# FPGA.net
KiCad netlist of a schematic drawn in Altium Designer
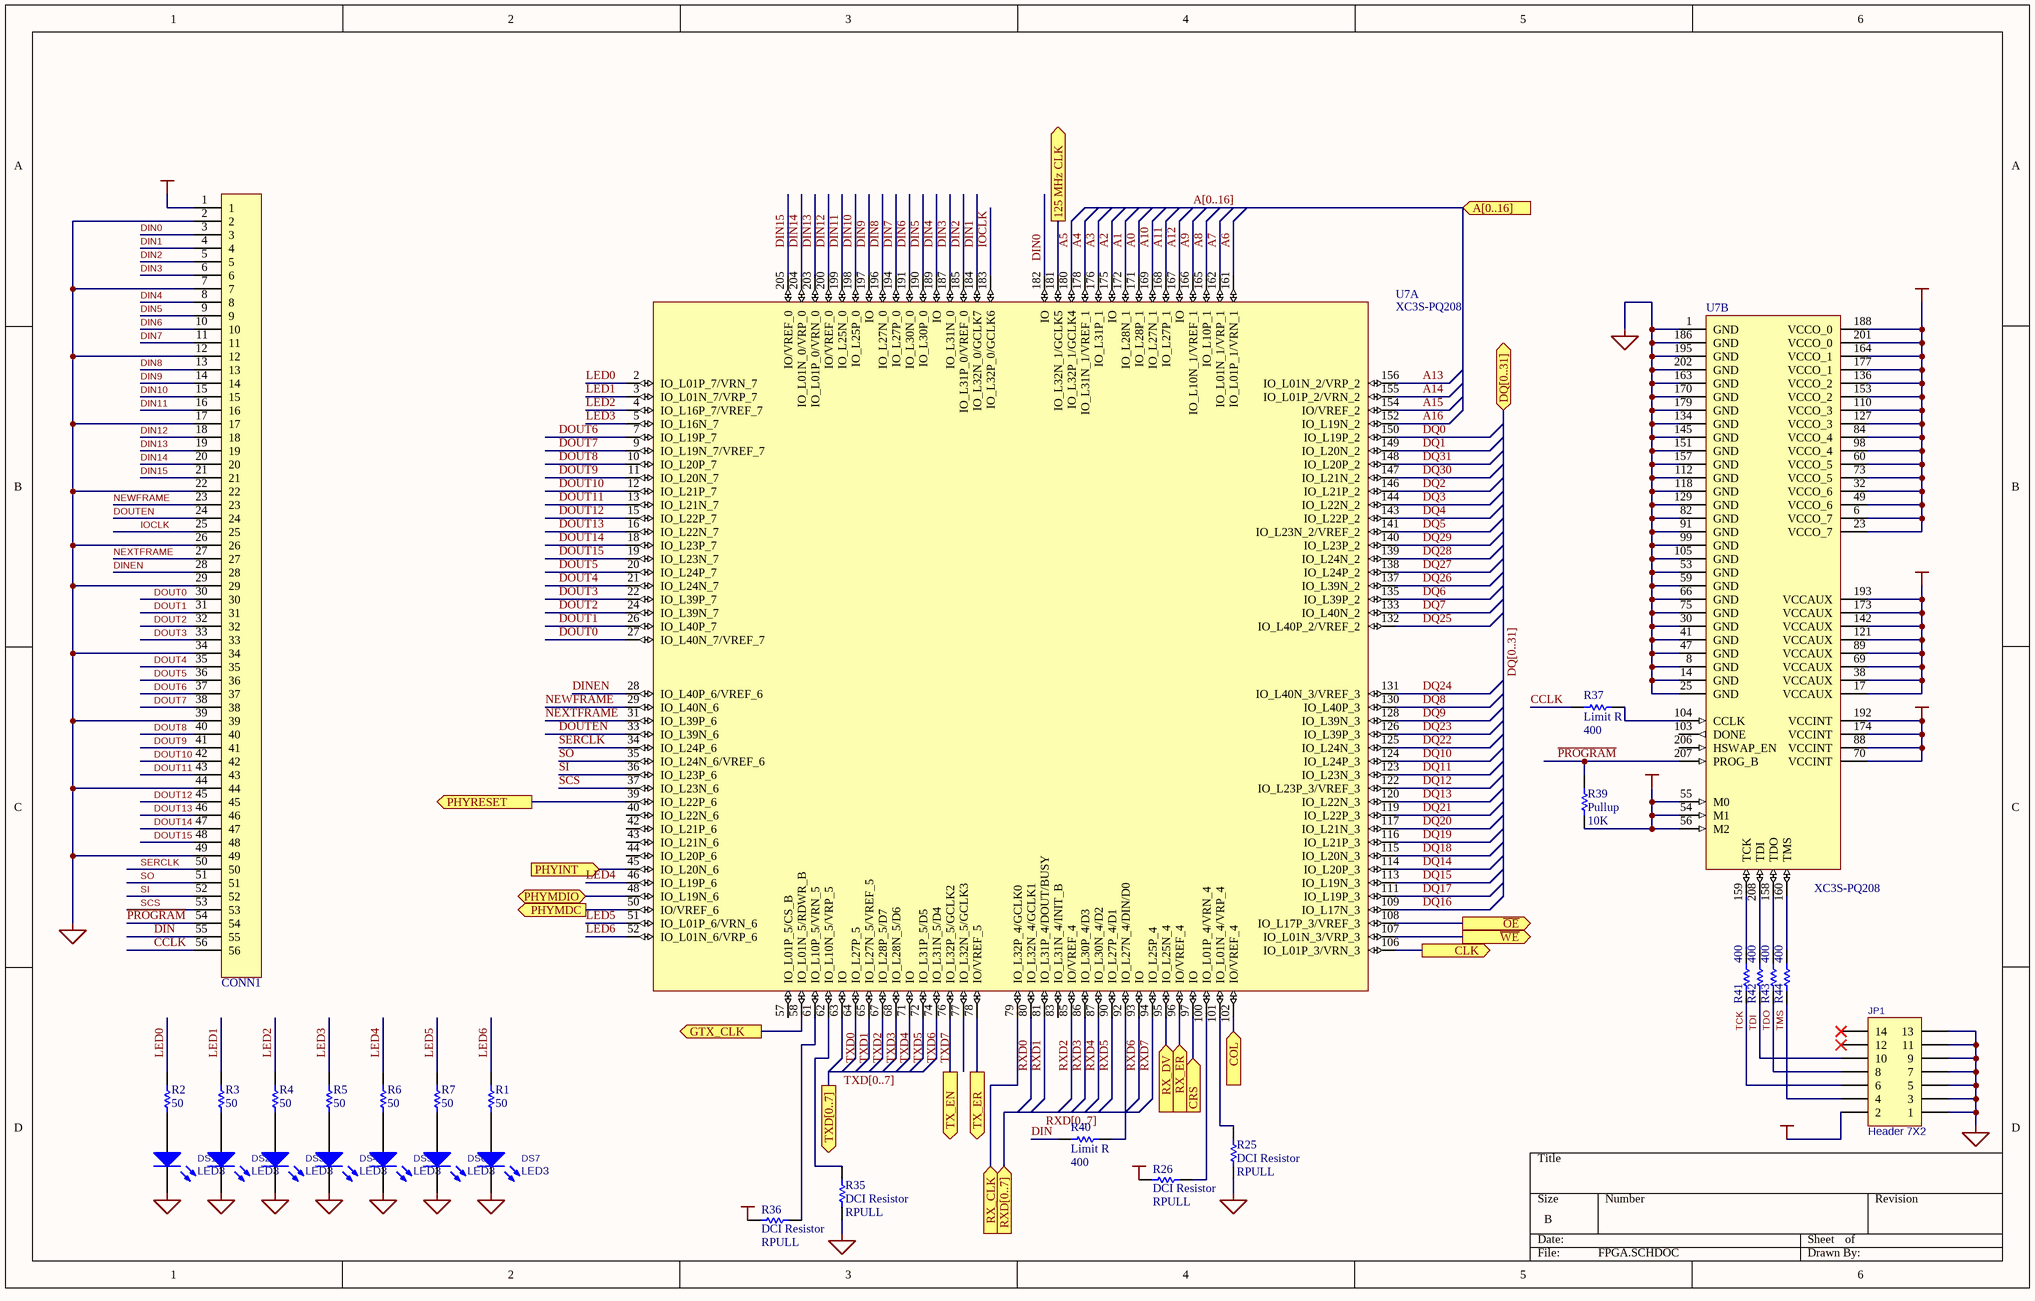
[diagram p0: FPGA.SCHDOC]

(export (version "E")
  (design (tool "Eeschema 10.0.6"))
  (components
    (comp (ref "CONN1") (value "CON56B") (footprint "HDR56F") (libsource (lib "parts") (part "CON56B")))
    (comp (ref "DS1")
      (value "LED3")
      (footprint "SMD _LED")
      (description "Typical BLUE SiC LED")
      (fields (field (name "PUBLISHER") "Altium Limited"))
      (libsource (lib "Miscellaneous Devices") (part "LED3"))
    )
    (comp (ref "DS2")
      (value "LED3")
      (footprint "SMD _LED")
      (description "Typical BLUE SiC LED")
      (fields (field (name "PUBLISHER") "Altium Limited"))
      (libsource (lib "Miscellaneous Devices") (part "LED3"))
    )
    (comp (ref "DS3")
      (value "LED3")
      (footprint "SMD _LED")
      (description "Typical BLUE SiC LED")
      (fields (field (name "PUBLISHER") "Altium Limited"))
      (libsource (lib "Miscellaneous Devices") (part "LED3"))
    )
    (comp (ref "DS4")
      (value "LED3")
      (footprint "SMD _LED")
      (description "Typical BLUE SiC LED")
      (fields (field (name "PUBLISHER") "Altium Limited"))
      (libsource (lib "Miscellaneous Devices") (part "LED3"))
    )
    (comp (ref "DS5")
      (value "LED3")
      (footprint "SMD _LED")
      (description "Typical BLUE SiC LED")
      (fields (field (name "PUBLISHER") "Altium Limited"))
      (libsource (lib "Miscellaneous Devices") (part "LED3"))
    )
    (comp (ref "DS6")
      (value "LED3")
      (footprint "SMD _LED")
      (description "Typical BLUE SiC LED")
      (fields (field (name "PUBLISHER") "Altium Limited"))
      (libsource (lib "Miscellaneous Devices") (part "LED3"))
    )
    (comp (ref "DS7")
      (value "LED3")
      (footprint "SMD _LED")
      (description "Typical BLUE SiC LED")
      (fields (field (name "PUBLISHER") "Altium Limited"))
      (libsource (lib "Miscellaneous Devices") (part "LED3"))
    )
    (comp (ref "JP1")
      (value "Header 7X2")
      (footprint "HDR2x7-2mm")
      (description "Header, 7-Pin, Dual row")
      (fields (field (name "MANUFACTURER") "Generic Components") (field (name "PUBLISHER") "Altium Limited"))
      (libsource (lib "Miscellaneous Connectors") (part "Header 7X2"))
    )
    (comp (ref "R1")
      (value "50")
      (footprint "0603")
      (description "Standard Passive Resistor")
      (fields (field (name "Comment") "RESISTOR"))
      (libsource (lib "parts") (part "RESISTOR"))
    )
    (comp (ref "R2")
      (value "50")
      (footprint "0603")
      (description "Standard Passive Resistor")
      (fields (field (name "Comment") "RESISTOR"))
      (libsource (lib "parts") (part "RESISTOR"))
    )
    (comp (ref "R3")
      (value "50")
      (footprint "0603")
      (description "Standard Passive Resistor")
      (fields (field (name "Comment") "RESISTOR"))
      (libsource (lib "parts") (part "RESISTOR"))
    )
    (comp (ref "R4")
      (value "50")
      (footprint "0603")
      (description "Standard Passive Resistor")
      (fields (field (name "Comment") "RESISTOR"))
      (libsource (lib "parts") (part "RESISTOR"))
    )
    (comp (ref "R5")
      (value "50")
      (footprint "0603")
      (description "Standard Passive Resistor")
      (fields (field (name "Comment") "RESISTOR"))
      (libsource (lib "parts") (part "RESISTOR"))
    )
    (comp (ref "R6")
      (value "50")
      (footprint "0603")
      (description "Standard Passive Resistor")
      (fields (field (name "Comment") "RESISTOR"))
      (libsource (lib "parts") (part "RESISTOR"))
    )
    (comp (ref "R7")
      (value "50")
      (footprint "0603")
      (description "Standard Passive Resistor")
      (fields (field (name "Comment") "RESISTOR"))
      (libsource (lib "parts") (part "RESISTOR"))
    )
    (comp (ref "R25")
      (value "DCI Resistor")
      (footprint "0603")
      (description "Resistor")
      (fields
        (field (name "MANUFACTURER") "Generic Components")
        (field (name "ALTIUM_VALUE") "RPULL")
        (field (name "PUBLISHER") "Altium Limited")
      )
      (libsource (lib "Miscellaneous Devices") (part "Res1"))
    )
    (comp (ref "R26")
      (value "DCI Resistor")
      (footprint "0603")
      (description "Resistor")
      (fields
        (field (name "MANUFACTURER") "Generic Components")
        (field (name "ALTIUM_VALUE") "RPULL")
        (field (name "PUBLISHER") "Altium Limited")
      )
      (libsource (lib "Miscellaneous Devices") (part "Res1"))
    )
    (comp (ref "R35")
      (value "DCI Resistor")
      (footprint "0603")
      (description "Resistor")
      (fields
        (field (name "MANUFACTURER") "Generic Components")
        (field (name "ALTIUM_VALUE") "RPULL")
        (field (name "PUBLISHER") "Altium Limited")
      )
      (libsource (lib "Miscellaneous Devices") (part "Res1"))
    )
    (comp (ref "R36")
      (value "DCI Resistor")
      (footprint "0603")
      (description "Resistor")
      (fields
        (field (name "MANUFACTURER") "Generic Components")
        (field (name "ALTIUM_VALUE") "RPULL")
        (field (name "PUBLISHER") "Altium Limited")
      )
      (libsource (lib "Miscellaneous Devices") (part "Res1"))
    )
    (comp (ref "R37")
      (value "Limit R")
      (footprint "0603")
      (description "Standard Passive Resistor")
      (fields (field (name "ALTIUM_VALUE") "400"))
      (libsource (lib "parts") (part "RESISTOR"))
    )
    (comp (ref "R39")
      (value "Pullup")
      (footprint "0603")
      (description "Resistor")
      (fields
        (field (name "MANUFACTURER") "Generic Components")
        (field (name "ALTIUM_VALUE") "10K")
        (field (name "PUBLISHER") "Altium Limited")
      )
      (libsource (lib "Miscellaneous Devices") (part "Res1"))
    )
    (comp (ref "R40")
      (value "Limit R")
      (footprint "0603")
      (description "Standard Passive Resistor")
      (fields (field (name "ALTIUM_VALUE") "400"))
      (libsource (lib "parts") (part "RESISTOR"))
    )
    (comp (ref "R41")
      (value "400")
      (footprint "0603")
      (description "Standard Passive Resistor")
      (fields (field (name "Comment") "RESISTOR"))
      (libsource (lib "parts") (part "RESISTOR"))
    )
    (comp (ref "R42")
      (value "400")
      (footprint "0603")
      (description "Standard Passive Resistor")
      (fields (field (name "Comment") "RESISTOR"))
      (libsource (lib "parts") (part "RESISTOR"))
    )
    (comp (ref "R43")
      (value "400")
      (footprint "0603")
      (description "Standard Passive Resistor")
      (fields (field (name "Comment") "RESISTOR"))
      (libsource (lib "parts") (part "RESISTOR"))
    )
    (comp (ref "R44")
      (value "400")
      (footprint "0603")
      (description "Standard Passive Resistor")
      (fields (field (name "Comment") "RESISTOR"))
      (libsource (lib "parts") (part "RESISTOR"))
    )
    (comp (ref "U7")
      (value "XC3S-PQ208")
      (footprint "F-QFP28X28-G208/Z32N")
      (description "Xilinx Spartan-3 PQ208")
      (libsource (lib "My devices") (part "XC3S-PQ208"))
    )
  )
  (nets
    (net (code "1") (name "+1.2VCC") (class "Default")
      (node (ref "U7") (pin "174") (pinfunction "VCCINT_174") (pintype "power_in"))
      (node (ref "U7") (pin "192") (pinfunction "VCCINT_192") (pintype "power_in"))
      (node (ref "U7") (pin "70") (pinfunction "VCCINT_70") (pintype "power_in"))
      (node (ref "U7") (pin "88") (pinfunction "VCCINT_88") (pintype "power_in"))
    )
    (net (code "2") (name "+2.5VCC") (class "Default")
      (node (ref "U7") (pin "121") (pinfunction "VCCAUX_121") (pintype "power_in"))
      (node (ref "U7") (pin "142") (pinfunction "VCCAUX_142") (pintype "power_in"))
      (node (ref "U7") (pin "17") (pinfunction "VCCAUX_17") (pintype "power_in"))
      (node (ref "U7") (pin "173") (pinfunction "VCCAUX_173") (pintype "power_in"))
      (node (ref "U7") (pin "193") (pinfunction "VCCAUX_193") (pintype "power_in"))
      (node (ref "U7") (pin "38") (pinfunction "VCCAUX_38") (pintype "power_in"))
      (node (ref "U7") (pin "69") (pinfunction "VCCAUX_69") (pintype "power_in"))
      (node (ref "U7") (pin "89") (pinfunction "VCCAUX_89") (pintype "power_in"))
    )
    (net (code "3") (name "/125 MHz CLK") (class "Default")
      (node (ref "U7") (pin "181") (pinfunction "IO_L32N_1/GCLK5_181") (pintype "bidirectional"))
    )
    (net (code "4") (name "/A0") (class "Default")
      (node (ref "U7") (pin "171") (pinfunction "IO_L28P_1_171") (pintype "bidirectional"))
    )
    (net (code "5") (name "/A1") (class "Default")
      (node (ref "U7") (pin "172") (pinfunction "IO_L28N_1_172") (pintype "bidirectional"))
    )
    (net (code "6") (name "/A2") (class "Default")
      (node (ref "U7") (pin "175") (pinfunction "IO_175") (pintype "bidirectional"))
    )
    (net (code "7") (name "/A3") (class "Default")
      (node (ref "U7") (pin "176") (pinfunction "IO_L31P_1_176") (pintype "bidirectional"))
    )
    (net (code "8") (name "/A4") (class "Default")
      (node (ref "U7") (pin "178") (pinfunction "IO_L31N_1/VREF_1_178") (pintype "bidirectional"))
    )
    (net (code "9") (name "/A5") (class "Default")
      (node (ref "U7") (pin "180") (pinfunction "IO_L32P_1/GCLK4_180") (pintype "bidirectional"))
    )
    (net (code "10") (name "/A6") (class "Default")
      (node (ref "U7") (pin "161") (pinfunction "IO_L01P_1/VRN_1_161") (pintype "bidirectional"))
    )
    (net (code "11") (name "/A7") (class "Default")
      (node (ref "U7") (pin "162") (pinfunction "IO_L01N_1/VRP_1_162") (pintype "bidirectional"))
    )
    (net (code "12") (name "/A8") (class "Default")
      (node (ref "U7") (pin "165") (pinfunction "IO_L10P_1_165") (pintype "bidirectional"))
    )
    (net (code "13") (name "/A9") (class "Default")
      (node (ref "U7") (pin "166") (pinfunction "IO_L10N_1/VREF_1_166") (pintype "bidirectional"))
    )
    (net (code "14") (name "/A10") (class "Default")
      (node (ref "U7") (pin "169") (pinfunction "IO_L27N_1_169") (pintype "bidirectional"))
    )
    (net (code "15") (name "/A11") (class "Default")
      (node (ref "U7") (pin "168") (pinfunction "IO_L27P_1_168") (pintype "bidirectional"))
    )
    (net (code "16") (name "/A12") (class "Default")
      (node (ref "U7") (pin "167") (pinfunction "IO_167") (pintype "bidirectional"))
    )
    (net (code "17") (name "/A13") (class "Default")
      (node (ref "U7") (pin "156") (pinfunction "IO_L01N_2/VRP_2_156") (pintype "bidirectional"))
    )
    (net (code "18") (name "/A14") (class "Default")
      (node (ref "U7") (pin "155") (pinfunction "IO_L01P_2/VRN_2_155") (pintype "bidirectional"))
    )
    (net (code "19") (name "/A15") (class "Default")
      (node (ref "U7") (pin "154") (pinfunction "IO/VREF_2_154") (pintype "bidirectional"))
    )
    (net (code "20") (name "/A16") (class "Default")
      (node (ref "U7") (pin "152") (pinfunction "IO_L19N_2_152") (pintype "bidirectional"))
    )
    (net (code "22") (name "/CCLK") (class "Default")
      (node (ref "CONN1") (pin "56") (pinfunction "56_56") (pintype "passive"))
      (node (ref "R37") (pin "2") (pintype "passive"))
    )
    (net (code "23") (name "/CLK") (class "Default")
      (node (ref "U7") (pin "106") (pinfunction "IO_L01P_3/VRN_3_106") (pintype "bidirectional"))
    )
    (net (code "24") (name "/COL") (class "Default")
      (node (ref "U7") (pin "102") (pinfunction "IO/VREF_4_102") (pintype "bidirectional"))
    )
    (net (code "25") (name "/CRS") (class "Default")
      (node (ref "U7") (pin "97") (pinfunction "IO_97") (pintype "bidirectional"))
    )
    (net (code "26") (name "/DIN") (class "Default")
      (node (ref "CONN1") (pin "55") (pinfunction "55_55") (pintype "passive"))
      (node (ref "R40") (pin "2") (pintype "passive"))
    )
    (net (code "27") (name "/DIN0") (class "Default")
      (node (ref "CONN1") (pin "3") (pinfunction "3_3") (pintype "passive"))
      (node (ref "U7") (pin "182") (pinfunction "IO_182") (pintype "bidirectional"))
    )
    (net (code "28") (name "/DIN1") (class "Default")
      (node (ref "CONN1") (pin "4") (pinfunction "4_4") (pintype "passive"))
      (node (ref "U7") (pin "184") (pinfunction "IO_L32N_0/GCLK7_184") (pintype "bidirectional"))
    )
    (net (code "29") (name "/DIN2") (class "Default")
      (node (ref "CONN1") (pin "5") (pinfunction "5_5") (pintype "passive"))
      (node (ref "U7") (pin "185") (pinfunction "IO_L31P_0/VREF_0_185") (pintype "bidirectional"))
    )
    (net (code "30") (name "/DIN3") (class "Default")
      (node (ref "CONN1") (pin "6") (pinfunction "6_6") (pintype "passive"))
      (node (ref "U7") (pin "187") (pinfunction "IO_L31N_0_187") (pintype "bidirectional"))
    )
    (net (code "31") (name "/DIN4") (class "Default")
      (node (ref "CONN1") (pin "8") (pinfunction "8_8") (pintype "passive"))
      (node (ref "U7") (pin "189") (pinfunction "IO_189") (pintype "bidirectional"))
    )
    (net (code "32") (name "/DIN5") (class "Default")
      (node (ref "CONN1") (pin "9") (pinfunction "9_9") (pintype "passive"))
      (node (ref "U7") (pin "190") (pinfunction "IO_L30P_0_190") (pintype "bidirectional"))
    )
    (net (code "33") (name "/DIN6") (class "Default")
      (node (ref "CONN1") (pin "10") (pinfunction "10_10") (pintype "passive"))
      (node (ref "U7") (pin "191") (pinfunction "IO_L30N_0_191") (pintype "bidirectional"))
    )
    (net (code "34") (name "/DIN7") (class "Default")
      (node (ref "CONN1") (pin "11") (pinfunction "11_11") (pintype "passive"))
      (node (ref "U7") (pin "194") (pinfunction "IO_L27P_0_194") (pintype "bidirectional"))
    )
    (net (code "35") (name "/DIN8") (class "Default")
      (node (ref "CONN1") (pin "13") (pinfunction "13_13") (pintype "passive"))
      (node (ref "U7") (pin "196") (pinfunction "IO_L27N_0_196") (pintype "bidirectional"))
    )
    (net (code "36") (name "/DIN9") (class "Default")
      (node (ref "CONN1") (pin "14") (pinfunction "14_14") (pintype "passive"))
      (node (ref "U7") (pin "197") (pinfunction "IO_197") (pintype "bidirectional"))
    )
    (net (code "37") (name "/DIN10") (class "Default")
      (node (ref "CONN1") (pin "15") (pinfunction "15_15") (pintype "passive"))
      (node (ref "U7") (pin "198") (pinfunction "IO_L25P_0_198") (pintype "bidirectional"))
    )
    (net (code "38") (name "/DIN11") (class "Default")
      (node (ref "CONN1") (pin "16") (pinfunction "16_16") (pintype "passive"))
      (node (ref "U7") (pin "199") (pinfunction "IO_L25N_0_199") (pintype "bidirectional"))
    )
    (net (code "39") (name "/DIN12") (class "Default")
      (node (ref "CONN1") (pin "18") (pinfunction "18_18") (pintype "passive"))
      (node (ref "U7") (pin "200") (pinfunction "IO/VREF_0_200") (pintype "bidirectional"))
    )
    (net (code "40") (name "/DIN13") (class "Default")
      (node (ref "CONN1") (pin "19") (pinfunction "19_19") (pintype "passive"))
      (node (ref "U7") (pin "203") (pinfunction "IO_L01P_0/VRN_0_203") (pintype "bidirectional"))
    )
    (net (code "41") (name "/DIN14") (class "Default")
      (node (ref "CONN1") (pin "20") (pinfunction "20_20") (pintype "passive"))
      (node (ref "U7") (pin "204") (pinfunction "IO_L01N_0/VRP_0_204") (pintype "bidirectional"))
    )
    (net (code "42") (name "/DIN15") (class "Default")
      (node (ref "CONN1") (pin "21") (pinfunction "21_21") (pintype "passive"))
      (node (ref "U7") (pin "205") (pinfunction "IO/VREF_0_205") (pintype "bidirectional"))
    )
    (net (code "43") (name "/DINEN") (class "Default")
      (node (ref "CONN1") (pin "28") (pinfunction "28_28") (pintype "passive"))
      (node (ref "U7") (pin "28") (pinfunction "IO_L40P_6/VREF_6_28") (pintype "bidirectional"))
    )
    (net (code "44") (name "/DOUT0") (class "Default")
      (node (ref "CONN1") (pin "30") (pinfunction "30_30") (pintype "passive"))
      (node (ref "U7") (pin "27") (pinfunction "IO_L40N_7/VREF_7_27") (pintype "bidirectional"))
    )
    (net (code "45") (name "/DOUT1") (class "Default")
      (node (ref "CONN1") (pin "31") (pinfunction "31_31") (pintype "passive"))
      (node (ref "U7") (pin "26") (pinfunction "IO_L40P_7_26") (pintype "bidirectional"))
    )
    (net (code "46") (name "/DOUT2") (class "Default")
      (node (ref "CONN1") (pin "32") (pinfunction "32_32") (pintype "passive"))
      (node (ref "U7") (pin "24") (pinfunction "IO_L39N_7_24") (pintype "bidirectional"))
    )
    (net (code "47") (name "/DOUT3") (class "Default")
      (node (ref "CONN1") (pin "33") (pinfunction "33_33") (pintype "passive"))
      (node (ref "U7") (pin "22") (pinfunction "IO_L39P_7_22") (pintype "bidirectional"))
    )
    (net (code "48") (name "/DOUT4") (class "Default")
      (node (ref "CONN1") (pin "35") (pinfunction "35_35") (pintype "passive"))
      (node (ref "U7") (pin "21") (pinfunction "IO_L24N_7_21") (pintype "bidirectional"))
    )
    (net (code "49") (name "/DOUT5") (class "Default")
      (node (ref "CONN1") (pin "36") (pinfunction "36_36") (pintype "passive"))
      (node (ref "U7") (pin "20") (pinfunction "IO_L24P_7_20") (pintype "bidirectional"))
    )
    (net (code "50") (name "/DOUT6") (class "Default")
      (node (ref "CONN1") (pin "37") (pinfunction "37_37") (pintype "passive"))
      (node (ref "U7") (pin "7") (pinfunction "IO_L19P_7_7") (pintype "bidirectional"))
    )
    (net (code "51") (name "/DOUT7") (class "Default")
      (node (ref "CONN1") (pin "38") (pinfunction "38_38") (pintype "passive"))
      (node (ref "U7") (pin "9") (pinfunction "IO_L19N_7/VREF_7_9") (pintype "bidirectional"))
    )
    (net (code "52") (name "/DOUT8") (class "Default")
      (node (ref "CONN1") (pin "40") (pinfunction "40_40") (pintype "passive"))
      (node (ref "U7") (pin "10") (pinfunction "IO_L20P_7_10") (pintype "bidirectional"))
    )
    (net (code "53") (name "/DOUT9") (class "Default")
      (node (ref "CONN1") (pin "41") (pinfunction "41_41") (pintype "passive"))
      (node (ref "U7") (pin "11") (pinfunction "IO_L20N_7_11") (pintype "bidirectional"))
    )
    (net (code "54") (name "/DOUT10") (class "Default")
      (node (ref "CONN1") (pin "42") (pinfunction "42_42") (pintype "passive"))
      (node (ref "U7") (pin "12") (pinfunction "IO_L21P_7_12") (pintype "bidirectional"))
    )
    (net (code "55") (name "/DOUT11") (class "Default")
      (node (ref "CONN1") (pin "43") (pinfunction "43_43") (pintype "passive"))
      (node (ref "U7") (pin "13") (pinfunction "IO_L21N_7_13") (pintype "bidirectional"))
    )
    (net (code "56") (name "/DOUT12") (class "Default")
      (node (ref "CONN1") (pin "45") (pinfunction "45_45") (pintype "passive"))
      (node (ref "U7") (pin "15") (pinfunction "IO_L22P_7_15") (pintype "bidirectional"))
    )
    (net (code "57") (name "/DOUT13") (class "Default")
      (node (ref "CONN1") (pin "46") (pinfunction "46_46") (pintype "passive"))
      (node (ref "U7") (pin "16") (pinfunction "IO_L22N_7_16") (pintype "bidirectional"))
    )
    (net (code "58") (name "/DOUT14") (class "Default")
      (node (ref "CONN1") (pin "47") (pinfunction "47_47") (pintype "passive"))
      (node (ref "U7") (pin "18") (pinfunction "IO_L23P_7_18") (pintype "bidirectional"))
    )
    (net (code "59") (name "/DOUT15") (class "Default")
      (node (ref "CONN1") (pin "48") (pinfunction "48_48") (pintype "passive"))
      (node (ref "U7") (pin "19") (pinfunction "IO_L23N_7_19") (pintype "bidirectional"))
    )
    (net (code "60") (name "/DOUTEN") (class "Default")
      (node (ref "CONN1") (pin "24") (pinfunction "24_24") (pintype "passive"))
      (node (ref "U7") (pin "33") (pinfunction "IO_L39N_6_33") (pintype "bidirectional"))
    )
    (net (code "61") (name "/DQ0") (class "Default")
      (node (ref "U7") (pin "150") (pinfunction "IO_L19P_2_150") (pintype "bidirectional"))
    )
    (net (code "62") (name "/DQ1") (class "Default")
      (node (ref "U7") (pin "149") (pinfunction "IO_L20N_2_149") (pintype "bidirectional"))
    )
    (net (code "63") (name "/DQ2") (class "Default")
      (node (ref "U7") (pin "146") (pinfunction "IO_L21P_2_146") (pintype "bidirectional"))
    )
    (net (code "64") (name "/DQ3") (class "Default")
      (node (ref "U7") (pin "144") (pinfunction "IO_L22N_2_144") (pintype "bidirectional"))
    )
    (net (code "65") (name "/DQ4") (class "Default")
      (node (ref "U7") (pin "143") (pinfunction "IO_L22P_2_143") (pintype "bidirectional"))
    )
    (net (code "66") (name "/DQ5") (class "Default")
      (node (ref "U7") (pin "141") (pinfunction "IO_L23N_2/VREF_2_141") (pintype "bidirectional"))
    )
    (net (code "67") (name "/DQ6") (class "Default")
      (node (ref "U7") (pin "135") (pinfunction "IO_L39P_2_135") (pintype "bidirectional"))
    )
    (net (code "68") (name "/DQ7") (class "Default")
      (node (ref "U7") (pin "133") (pinfunction "IO_L40N_2_133") (pintype "bidirectional"))
    )
    (net (code "69") (name "/DQ8") (class "Default")
      (node (ref "U7") (pin "130") (pinfunction "IO_L40P_3_130") (pintype "bidirectional"))
    )
    (net (code "70") (name "/DQ9") (class "Default")
      (node (ref "U7") (pin "128") (pinfunction "IO_L39N_3_128") (pintype "bidirectional"))
    )
    (net (code "71") (name "/DQ10") (class "Default")
      (node (ref "U7") (pin "124") (pinfunction "IO_L24P_3_124") (pintype "bidirectional"))
    )
    (net (code "72") (name "/DQ11") (class "Default")
      (node (ref "U7") (pin "123") (pinfunction "IO_L23N_3_123") (pintype "bidirectional"))
    )
    (net (code "73") (name "/DQ12") (class "Default")
      (node (ref "U7") (pin "122") (pinfunction "IO_L23P_3/VREF_3_122") (pintype "bidirectional"))
    )
    (net (code "74") (name "/DQ13") (class "Default")
      (node (ref "U7") (pin "120") (pinfunction "IO_L22N_3_120") (pintype "bidirectional"))
    )
    (net (code "75") (name "/DQ14") (class "Default")
      (node (ref "U7") (pin "114") (pinfunction "IO_L20P_3_114") (pintype "bidirectional"))
    )
    (net (code "76") (name "/DQ15") (class "Default")
      (node (ref "U7") (pin "113") (pinfunction "IO_L19N_3_113") (pintype "bidirectional"))
    )
    (net (code "77") (name "/DQ16") (class "Default")
      (node (ref "U7") (pin "109") (pinfunction "IO_L17N_3_109") (pintype "bidirectional"))
    )
    (net (code "78") (name "/DQ17") (class "Default")
      (node (ref "U7") (pin "111") (pinfunction "IO_L19P_3_111") (pintype "bidirectional"))
    )
    (net (code "79") (name "/DQ18") (class "Default")
      (node (ref "U7") (pin "115") (pinfunction "IO_L20N_3_115") (pintype "bidirectional"))
    )
    (net (code "80") (name "/DQ19") (class "Default")
      (node (ref "U7") (pin "116") (pinfunction "IO_L21P_3_116") (pintype "bidirectional"))
    )
    (net (code "81") (name "/DQ20") (class "Default")
      (node (ref "U7") (pin "117") (pinfunction "IO_L21N_3_117") (pintype "bidirectional"))
    )
    (net (code "82") (name "/DQ21") (class "Default")
      (node (ref "U7") (pin "119") (pinfunction "IO_L22P_3_119") (pintype "bidirectional"))
    )
    (net (code "83") (name "/DQ22") (class "Default")
      (node (ref "U7") (pin "125") (pinfunction "IO_L24N_3_125") (pintype "bidirectional"))
    )
    (net (code "84") (name "/DQ23") (class "Default")
      (node (ref "U7") (pin "126") (pinfunction "IO_L39P_3_126") (pintype "bidirectional"))
    )
    (net (code "85") (name "/DQ24") (class "Default")
      (node (ref "U7") (pin "131") (pinfunction "IO_L40N_3/VREF_3_131") (pintype "bidirectional"))
    )
    (net (code "86") (name "/DQ25") (class "Default")
      (node (ref "U7") (pin "132") (pinfunction "IO_L40P_2/VREF_2_132") (pintype "bidirectional"))
    )
    (net (code "87") (name "/DQ26") (class "Default")
      (node (ref "U7") (pin "137") (pinfunction "IO_L39N_2_137") (pintype "bidirectional"))
    )
    (net (code "88") (name "/DQ27") (class "Default")
      (node (ref "U7") (pin "138") (pinfunction "IO_L24P_2_138") (pintype "bidirectional"))
    )
    (net (code "89") (name "/DQ28") (class "Default")
      (node (ref "U7") (pin "139") (pinfunction "IO_L24N_2_139") (pintype "bidirectional"))
    )
    (net (code "90") (name "/DQ29") (class "Default")
      (node (ref "U7") (pin "140") (pinfunction "IO_L23P_2_140") (pintype "bidirectional"))
    )
    (net (code "91") (name "/DQ30") (class "Default")
      (node (ref "U7") (pin "147") (pinfunction "IO_L21N_2_147") (pintype "bidirectional"))
    )
    (net (code "92") (name "/DQ31") (class "Default")
      (node (ref "U7") (pin "148") (pinfunction "IO_L20P_2_148") (pintype "bidirectional"))
    )
    (net (code "94") (name "/GTX_CLK") (class "Default")
      (node (ref "U7") (pin "58") (pinfunction "IO_L01N_5/RDWR_B_58") (pintype "bidirectional"))
    )
    (net (code "95") (name "/IOCLK") (class "Default")
      (node (ref "CONN1") (pin "25") (pinfunction "25_25") (pintype "passive"))
      (node (ref "U7") (pin "183") (pinfunction "IO_L32P_0/GCLK6_183") (pintype "bidirectional"))
    )
    (net (code "96") (name "/LED0") (class "Default")
      (node (ref "R2") (pin "2") (pintype "passive"))
      (node (ref "U7") (pin "2") (pinfunction "IO_L01P_7/VRN_7_2") (pintype "bidirectional"))
    )
    (net (code "97") (name "/LED1") (class "Default")
      (node (ref "R3") (pin "2") (pintype "passive"))
      (node (ref "U7") (pin "3") (pinfunction "IO_L01N_7/VRP_7_3") (pintype "bidirectional"))
    )
    (net (code "98") (name "/LED2") (class "Default")
      (node (ref "R4") (pin "2") (pintype "passive"))
      (node (ref "U7") (pin "4") (pinfunction "IO_L16P_7/VREF_7_4") (pintype "bidirectional"))
    )
    (net (code "99") (name "/LED3") (class "Default")
      (node (ref "R5") (pin "2") (pintype "passive"))
      (node (ref "U7") (pin "5") (pinfunction "IO_L16N_7_5") (pintype "bidirectional"))
    )
    (net (code "100") (name "/LED4") (class "Default")
      (node (ref "R6") (pin "2") (pintype "passive"))
      (node (ref "U7") (pin "46") (pinfunction "IO_L19P_6_46") (pintype "bidirectional"))
    )
    (net (code "101") (name "/LED5") (class "Default")
      (node (ref "R7") (pin "2") (pintype "passive"))
      (node (ref "U7") (pin "51") (pinfunction "IO_L01P_6/VRN_6_51") (pintype "bidirectional"))
    )
    (net (code "102") (name "/LED6") (class "Default")
      (node (ref "R1") (pin "2") (pintype "passive"))
      (node (ref "U7") (pin "52") (pinfunction "IO_L01N_6/VRP_6_52") (pintype "bidirectional"))
    )
    (net (code "103") (name "/NEWFRAME") (class "Default")
      (node (ref "CONN1") (pin "23") (pinfunction "23_23") (pintype "passive"))
      (node (ref "U7") (pin "29") (pinfunction "IO_L40N_6_29") (pintype "bidirectional"))
    )
    (net (code "104") (name "/NEXTFRAME") (class "Default")
      (node (ref "CONN1") (pin "27") (pinfunction "27_27") (pintype "passive"))
      (node (ref "U7") (pin "31") (pinfunction "IO_L39P_6_31") (pintype "bidirectional"))
    )
    (net (code "105") (name "/PHYINT") (class "Default")
      (node (ref "U7") (pin "45") (pinfunction "IO_L20N_6_45") (pintype "bidirectional"))
    )
    (net (code "106") (name "/PHYMDC") (class "Default")
      (node (ref "U7") (pin "50") (pinfunction "IO/VREF_6_50") (pintype "bidirectional"))
    )
    (net (code "107") (name "/PHYMDIO") (class "Default")
      (node (ref "U7") (pin "48") (pinfunction "IO_L19N_6_48") (pintype "bidirectional"))
    )
    (net (code "108") (name "/PHYRESET") (class "Default")
      (node (ref "U7") (pin "39") (pinfunction "IO_L22P_6_39") (pintype "bidirectional"))
    )
    (net (code "109") (name "/RXD0") (class "Default")
      (node (ref "U7") (pin "80") (pinfunction "IO_L32N_4/GCLK1_80") (pintype "bidirectional"))
    )
    (net (code "110") (name "/RXD1") (class "Default")
      (node (ref "U7") (pin "81") (pinfunction "IO_L31P_4/DOUT/BUSY_81") (pintype "bidirectional"))
    )
    (net (code "111") (name "/RXD2") (class "Default")
      (node (ref "U7") (pin "85") (pinfunction "IO/VREF_4_85") (pintype "bidirectional"))
    )
    (net (code "112") (name "/RXD3") (class "Default")
      (node (ref "U7") (pin "86") (pinfunction "IO_L30P_4/D3_86") (pintype "bidirectional"))
    )
    (net (code "113") (name "/RXD4") (class "Default")
      (node (ref "U7") (pin "87") (pinfunction "IO_L30N_4/D2_87") (pintype "bidirectional"))
    )
    (net (code "114") (name "/RXD5") (class "Default")
      (node (ref "U7") (pin "90") (pinfunction "IO_L27P_4/D1_90") (pintype "bidirectional"))
    )
    (net (code "115") (name "/RXD6") (class "Default")
      (node (ref "U7") (pin "93") (pinfunction "IO_93") (pintype "bidirectional"))
    )
    (net (code "116") (name "/RXD7") (class "Default")
      (node (ref "U7") (pin "94") (pinfunction "IO_L25P_4_94") (pintype "bidirectional"))
    )
    (net (code "118") (name "/RX_CLK") (class "Default")
      (node (ref "U7") (pin "79") (pinfunction "IO_L32P_4/GCLK0_79") (pintype "bidirectional"))
    )
    (net (code "119") (name "/RX_DV") (class "Default")
      (node (ref "U7") (pin "95") (pinfunction "IO_L25N_4_95") (pintype "bidirectional"))
    )
    (net (code "120") (name "/RX_ER") (class "Default")
      (node (ref "U7") (pin "96") (pinfunction "IO/VREF_4_96") (pintype "bidirectional"))
    )
    (net (code "121") (name "/SCS") (class "Default")
      (node (ref "CONN1") (pin "53") (pinfunction "53_53") (pintype "passive"))
      (node (ref "U7") (pin "37") (pinfunction "IO_L23N_6_37") (pintype "bidirectional"))
    )
    (net (code "122") (name "/SERCLK") (class "Default")
      (node (ref "CONN1") (pin "50") (pinfunction "50_50") (pintype "passive"))
      (node (ref "U7") (pin "34") (pinfunction "IO_L24P_6_34") (pintype "bidirectional"))
    )
    (net (code "123") (name "/SI") (class "Default")
      (node (ref "CONN1") (pin "52") (pinfunction "52_52") (pintype "passive"))
      (node (ref "U7") (pin "36") (pinfunction "IO_L23P_6_36") (pintype "bidirectional"))
    )
    (net (code "124") (name "/SO") (class "Default")
      (node (ref "CONN1") (pin "51") (pinfunction "51_51") (pintype "passive"))
      (node (ref "U7") (pin "35") (pinfunction "IO_L24N_6/VREF_6_35") (pintype "bidirectional"))
    )
    (net (code "125") (name "/TCK") (class "Default")
      (node (ref "JP1") (pin "6") (pinfunction "6_6") (pintype "passive"))
      (node (ref "R41") (pin "2") (pintype "passive"))
    )
    (net (code "126") (name "/TDI") (class "Default")
      (node (ref "JP1") (pin "10") (pinfunction "10_10") (pintype "passive"))
      (node (ref "R42") (pin "2") (pintype "passive"))
    )
    (net (code "127") (name "/TDO") (class "Default")
      (node (ref "JP1") (pin "8") (pinfunction "8_8") (pintype "passive"))
      (node (ref "R43") (pin "2") (pintype "passive"))
    )
    (net (code "128") (name "/TMS") (class "Default")
      (node (ref "JP1") (pin "4") (pinfunction "4_4") (pintype "passive"))
      (node (ref "R44") (pin "2") (pintype "passive"))
    )
    (net (code "129") (name "/TXD0") (class "Default")
      (node (ref "U7") (pin "63") (pinfunction "IO_63") (pintype "bidirectional"))
    )
    (net (code "130") (name "/TXD1") (class "Default")
      (node (ref "U7") (pin "64") (pinfunction "IO_L27P_5_64") (pintype "bidirectional"))
    )
    (net (code "131") (name "/TXD2") (class "Default")
      (node (ref "U7") (pin "65") (pinfunction "IO_L27N_5/VREF_5_65") (pintype "bidirectional"))
    )
    (net (code "132") (name "/TXD3") (class "Default")
      (node (ref "U7") (pin "67") (pinfunction "IO_L28P_5/D7_67") (pintype "bidirectional"))
    )
    (net (code "133") (name "/TXD4") (class "Default")
      (node (ref "U7") (pin "68") (pinfunction "IO_L28N_5/D6_68") (pintype "bidirectional"))
    )
    (net (code "134") (name "/TXD5") (class "Default")
      (node (ref "U7") (pin "71") (pinfunction "IO_71") (pintype "bidirectional"))
    )
    (net (code "135") (name "/TXD6") (class "Default")
      (node (ref "U7") (pin "72") (pinfunction "IO_L31P_5/D5_72") (pintype "bidirectional"))
    )
    (net (code "136") (name "/TXD7") (class "Default")
      (node (ref "U7") (pin "74") (pinfunction "IO_L31N_5/D4_74") (pintype "bidirectional"))
    )
    (net (code "138") (name "/TX_EN") (class "Default")
      (node (ref "U7") (pin "76") (pinfunction "IO_L32P_5/GCLK2_76") (pintype "bidirectional"))
    )
    (net (code "139") (name "/TX_ER") (class "Default")
      (node (ref "U7") (pin "78") (pinfunction "IO/VREF_5_78") (pintype "bidirectional"))
    )
    (net (code "140") (name "/~{OE}") (class "Default")
      (node (ref "U7") (pin "108") (pinfunction "IO_L17P_3/VREF_3_108") (pintype "bidirectional"))
    )
    (net (code "141") (name "/~{PROGRAM}") (class "Default")
      (node (ref "CONN1") (pin "54") (pinfunction "54_54") (pintype "passive"))
      (node (ref "R39") (pin "1") (pinfunction "1_1") (pintype "passive"))
      (node (ref "U7") (pin "207") (pinfunction "PROG_B_207") (pintype "input"))
    )
    (net (code "142") (name "/~{WE}") (class "Default")
      (node (ref "U7") (pin "107") (pinfunction "IO_L01N_3/VRP_3_107") (pintype "bidirectional"))
    )
    (net (code "143") (name "GND") (class "Default")
      (node (ref "CONN1") (pin "12") (pinfunction "12_12") (pintype "passive"))
      (node (ref "CONN1") (pin "17") (pinfunction "17_17") (pintype "passive"))
      (node (ref "CONN1") (pin "2") (pinfunction "2_2") (pintype "passive"))
      (node (ref "CONN1") (pin "22") (pinfunction "22_22") (pintype "passive"))
      (node (ref "CONN1") (pin "26") (pinfunction "26_26") (pintype "passive"))
      (node (ref "CONN1") (pin "29") (pinfunction "29_29") (pintype "passive"))
      (node (ref "CONN1") (pin "34") (pinfunction "34_34") (pintype "passive"))
      (node (ref "CONN1") (pin "39") (pinfunction "39_39") (pintype "passive"))
      (node (ref "CONN1") (pin "44") (pinfunction "44_44") (pintype "passive"))
      (node (ref "CONN1") (pin "49") (pinfunction "49_49") (pintype "passive"))
      (node (ref "CONN1") (pin "7") (pinfunction "7_7") (pintype "passive"))
      (node (ref "DS1") (pin "2") (pinfunction "K_2") (pintype "passive"))
      (node (ref "DS2") (pin "2") (pinfunction "K_2") (pintype "passive"))
      (node (ref "DS3") (pin "2") (pinfunction "K_2") (pintype "passive"))
      (node (ref "DS4") (pin "2") (pinfunction "K_2") (pintype "passive"))
      (node (ref "DS5") (pin "2") (pinfunction "K_2") (pintype "passive"))
      (node (ref "DS6") (pin "2") (pinfunction "K_2") (pintype "passive"))
      (node (ref "DS7") (pin "2") (pinfunction "K_2") (pintype "passive"))
      (node (ref "JP1") (pin "1") (pinfunction "1_1") (pintype "passive"))
      (node (ref "JP1") (pin "11") (pinfunction "11_11") (pintype "passive"))
      (node (ref "JP1") (pin "13") (pinfunction "13_13") (pintype "passive"))
      (node (ref "JP1") (pin "3") (pinfunction "3_3") (pintype "passive"))
      (node (ref "JP1") (pin "5") (pinfunction "5_5") (pintype "passive"))
      (node (ref "JP1") (pin "7") (pinfunction "7_7") (pintype "passive"))
      (node (ref "JP1") (pin "9") (pinfunction "9_9") (pintype "passive"))
      (node (ref "R25") (pin "1") (pinfunction "1_1") (pintype "passive"))
      (node (ref "R35") (pin "1") (pinfunction "1_1") (pintype "passive"))
      (node (ref "U7") (pin "1") (pinfunction "GND_1") (pintype "power_in"))
      (node (ref "U7") (pin "105") (pinfunction "GND_105") (pintype "power_in"))
      (node (ref "U7") (pin "112") (pinfunction "GND_112") (pintype "power_in"))
      (node (ref "U7") (pin "118") (pinfunction "GND_118") (pintype "power_in"))
      (node (ref "U7") (pin "129") (pinfunction "GND_129") (pintype "power_in"))
      (node (ref "U7") (pin "134") (pinfunction "GND_134") (pintype "power_in"))
      (node (ref "U7") (pin "14") (pinfunction "GND_14") (pintype "power_in"))
      (node (ref "U7") (pin "145") (pinfunction "GND_145") (pintype "power_in"))
      (node (ref "U7") (pin "151") (pinfunction "GND_151") (pintype "power_in"))
      (node (ref "U7") (pin "157") (pinfunction "GND_157") (pintype "power_in"))
      (node (ref "U7") (pin "163") (pinfunction "GND_163") (pintype "power_in"))
      (node (ref "U7") (pin "170") (pinfunction "GND_170") (pintype "power_in"))
      (node (ref "U7") (pin "179") (pinfunction "GND_179") (pintype "power_in"))
      (node (ref "U7") (pin "186") (pinfunction "GND_186") (pintype "power_in"))
      (node (ref "U7") (pin "195") (pinfunction "GND_195") (pintype "power_in"))
      (node (ref "U7") (pin "202") (pinfunction "GND_202") (pintype "power_in"))
      (node (ref "U7") (pin "25") (pinfunction "GND_25") (pintype "power_in"))
      (node (ref "U7") (pin "30") (pinfunction "GND_30") (pintype "power_in"))
      (node (ref "U7") (pin "41") (pinfunction "GND_41") (pintype "power_in"))
      (node (ref "U7") (pin "47") (pinfunction "GND_47") (pintype "power_in"))
      (node (ref "U7") (pin "53") (pinfunction "GND_53") (pintype "power_in"))
      (node (ref "U7") (pin "59") (pinfunction "GND_59") (pintype "power_in"))
      (node (ref "U7") (pin "66") (pinfunction "GND_66") (pintype "power_in"))
      (node (ref "U7") (pin "75") (pinfunction "GND_75") (pintype "power_in"))
      (node (ref "U7") (pin "8") (pinfunction "GND_8") (pintype "power_in"))
      (node (ref "U7") (pin "82") (pinfunction "GND_82") (pintype "power_in"))
      (node (ref "U7") (pin "91") (pinfunction "GND_91") (pintype "power_in"))
      (node (ref "U7") (pin "99") (pinfunction "GND_99") (pintype "power_in"))
    )
    (net (code "144") (name "Net-(DS1-A)") (class "Default")
      (node (ref "DS1") (pin "1") (pinfunction "A_1") (pintype "passive"))
      (node (ref "R2") (pin "1") (pintype "passive"))
    )
    (net (code "145") (name "Net-(DS2-A)") (class "Default")
      (node (ref "DS2") (pin "1") (pinfunction "A_1") (pintype "passive"))
      (node (ref "R3") (pin "1") (pintype "passive"))
    )
    (net (code "146") (name "Net-(DS3-A)") (class "Default")
      (node (ref "DS3") (pin "1") (pinfunction "A_1") (pintype "passive"))
      (node (ref "R4") (pin "1") (pintype "passive"))
    )
    (net (code "147") (name "Net-(DS4-A)") (class "Default")
      (node (ref "DS4") (pin "1") (pinfunction "A_1") (pintype "passive"))
      (node (ref "R5") (pin "1") (pintype "passive"))
    )
    (net (code "148") (name "Net-(DS5-A)") (class "Default")
      (node (ref "DS5") (pin "1") (pinfunction "A_1") (pintype "passive"))
      (node (ref "R6") (pin "1") (pintype "passive"))
    )
    (net (code "149") (name "Net-(DS6-A)") (class "Default")
      (node (ref "DS6") (pin "1") (pinfunction "A_1") (pintype "passive"))
      (node (ref "R7") (pin "1") (pintype "passive"))
    )
    (net (code "150") (name "Net-(DS7-A)") (class "Default")
      (node (ref "DS7") (pin "1") (pinfunction "A_1") (pintype "passive"))
      (node (ref "R1") (pin "1") (pintype "passive"))
    )
    (net (code "151") (name "Net-(U7A-IO_L01N_4{slash}VRP_4)") (class "Default")
      (node (ref "R25") (pin "2") (pinfunction "2_2") (pintype "passive"))
      (node (ref "U7") (pin "101") (pinfunction "IO_L01N_4/VRP_4_101") (pintype "bidirectional"))
    )
    (net (code "152") (name "Net-(U7A-IO_L01P_4{slash}VRN_4)") (class "Default")
      (node (ref "R26") (pin "1") (pinfunction "1_1") (pintype "passive"))
      (node (ref "U7") (pin "100") (pinfunction "IO_L01P_4/VRN_4_100") (pintype "bidirectional"))
    )
    (net (code "153") (name "Net-(U7A-IO_L10N_5{slash}VRP_5)") (class "Default")
      (node (ref "R35") (pin "2") (pinfunction "2_2") (pintype "passive"))
      (node (ref "U7") (pin "62") (pinfunction "IO_L10N_5/VRP_5_62") (pintype "bidirectional"))
    )
    (net (code "154") (name "Net-(U7A-IO_L10P_5{slash}VRN_5)") (class "Default")
      (node (ref "R36") (pin "1") (pinfunction "1_1") (pintype "passive"))
      (node (ref "U7") (pin "61") (pinfunction "IO_L10P_5/VRN_5_61") (pintype "bidirectional"))
    )
    (net (code "155") (name "Net-(U7A-IO_L27N_4{slash}DIN{slash}D0)") (class "Default")
      (node (ref "R40") (pin "1") (pintype "passive"))
      (node (ref "U7") (pin "92") (pinfunction "IO_L27N_4/DIN/D0_92") (pintype "bidirectional"))
    )
    (net (code "156") (name "Net-(U7B-CCLK)") (class "Default")
      (node (ref "R37") (pin "1") (pintype "passive"))
      (node (ref "U7") (pin "104") (pinfunction "CCLK_104") (pintype "input"))
    )
    (net (code "157") (name "Net-(U7B-TCK)") (class "Default")
      (node (ref "R41") (pin "1") (pintype "passive"))
      (node (ref "U7") (pin "159") (pinfunction "TCK_159") (pintype "bidirectional"))
    )
    (net (code "158") (name "Net-(U7B-TDI)") (class "Default")
      (node (ref "R42") (pin "1") (pintype "passive"))
      (node (ref "U7") (pin "208") (pinfunction "TDI_208") (pintype "bidirectional"))
    )
    (net (code "159") (name "Net-(U7B-TDO)") (class "Default")
      (node (ref "R43") (pin "1") (pintype "passive"))
      (node (ref "U7") (pin "158") (pinfunction "TDO_158") (pintype "bidirectional"))
    )
    (net (code "160") (name "Net-(U7B-TMS)") (class "Default")
      (node (ref "R44") (pin "1") (pintype "passive"))
      (node (ref "U7") (pin "160") (pinfunction "TMS_160") (pintype "bidirectional"))
    )
    (net (code "161") (name "VCC") (class "Default")
      (node (ref "CONN1") (pin "1") (pinfunction "1_1") (pintype "passive"))
      (node (ref "JP1") (pin "2") (pinfunction "2_2") (pintype "passive"))
      (node (ref "R26") (pin "2") (pinfunction "2_2") (pintype "passive"))
      (node (ref "R36") (pin "2") (pinfunction "2_2") (pintype "passive"))
      (node (ref "R39") (pin "2") (pinfunction "2_2") (pintype "passive"))
      (node (ref "U7") (pin "110") (pinfunction "VCCO_3_110") (pintype "power_in"))
      (node (ref "U7") (pin "127") (pinfunction "VCCO_3_127") (pintype "power_in"))
      (node (ref "U7") (pin "136") (pinfunction "VCCO_2_136") (pintype "power_in"))
      (node (ref "U7") (pin "153") (pinfunction "VCCO_2_153") (pintype "power_in"))
      (node (ref "U7") (pin "164") (pinfunction "VCCO_1_164") (pintype "power_in"))
      (node (ref "U7") (pin "177") (pinfunction "VCCO_1_177") (pintype "power_in"))
      (node (ref "U7") (pin "188") (pinfunction "VCCO_0_188") (pintype "power_in"))
      (node (ref "U7") (pin "201") (pinfunction "VCCO_0_201") (pintype "power_in"))
      (node (ref "U7") (pin "23") (pinfunction "VCCO_7_23") (pintype "power_in"))
      (node (ref "U7") (pin "32") (pinfunction "VCCO_6_32") (pintype "power_in"))
      (node (ref "U7") (pin "49") (pinfunction "VCCO_6_49") (pintype "power_in"))
      (node (ref "U7") (pin "54") (pinfunction "M1_54") (pintype "input"))
      (node (ref "U7") (pin "55") (pinfunction "M0_55") (pintype "input"))
      (node (ref "U7") (pin "56") (pinfunction "M2_56") (pintype "input"))
      (node (ref "U7") (pin "6") (pinfunction "VCCO_7_6") (pintype "power_in"))
      (node (ref "U7") (pin "60") (pinfunction "VCCO_5_60") (pintype "power_in"))
      (node (ref "U7") (pin "73") (pinfunction "VCCO_5_73") (pintype "power_in"))
      (node (ref "U7") (pin "84") (pinfunction "VCCO_4_84") (pintype "power_in"))
      (node (ref "U7") (pin "98") (pinfunction "VCCO_4_98") (pintype "power_in"))
    )
    (net (code "162") (name "unconnected-(JP1-Pad12)") (class "Default")
      (node (ref "JP1") (pin "12") (pinfunction "12_12") (pintype "passive+no_connect"))
    )
    (net (code "163") (name "unconnected-(JP1-Pad14)") (class "Default")
      (node (ref "JP1") (pin "14") (pinfunction "14_14") (pintype "passive+no_connect"))
    )
    (net (code "164") (name "unconnected-(U7A-IO_L01P_5{slash}CS_B-Pad57)") (class "Default")
      (node (ref "U7") (pin "57") (pinfunction "IO_L01P_5/CS_B_57") (pintype "bidirectional"))
    )
    (net (code "165") (name "unconnected-(U7A-IO_L20P_6-Pad44)") (class "Default")
      (node (ref "U7") (pin "44") (pinfunction "IO_L20P_6_44") (pintype "bidirectional"))
    )
    (net (code "166") (name "unconnected-(U7A-IO_L21N_6-Pad43)") (class "Default")
      (node (ref "U7") (pin "43") (pinfunction "IO_L21N_6_43") (pintype "bidirectional"))
    )
    (net (code "167") (name "unconnected-(U7A-IO_L21P_6-Pad42)") (class "Default")
      (node (ref "U7") (pin "42") (pinfunction "IO_L21P_6_42") (pintype "bidirectional"))
    )
    (net (code "168") (name "unconnected-(U7A-IO_L22N_6-Pad40)") (class "Default")
      (node (ref "U7") (pin "40") (pinfunction "IO_L22N_6_40") (pintype "bidirectional"))
    )
    (net (code "169") (name "unconnected-(U7A-IO_L31N_4{slash}INIT_B-Pad83)") (class "Default")
      (node (ref "U7") (pin "83") (pinfunction "IO_L31N_4/INIT_B_83") (pintype "bidirectional"))
    )
    (net (code "170") (name "unconnected-(U7A-IO_L32N_5{slash}GCLK3-Pad77)") (class "Default")
      (node (ref "U7") (pin "77") (pinfunction "IO_L32N_5/GCLK3_77") (pintype "bidirectional"))
    )
    (net (code "171") (name "unconnected-(U7B-DONE-Pad103)") (class "Default")
      (node (ref "U7") (pin "103") (pinfunction "DONE_103") (pintype "output"))
    )
    (net (code "172") (name "unconnected-(U7B-HSWAP_EN-Pad206)") (class "Default")
      (node (ref "U7") (pin "206") (pinfunction "HSWAP_EN_206") (pintype "input"))
    )
  )
)
